# Poseidon.net
KiCad netlist of a schematic drawn in EAGLE
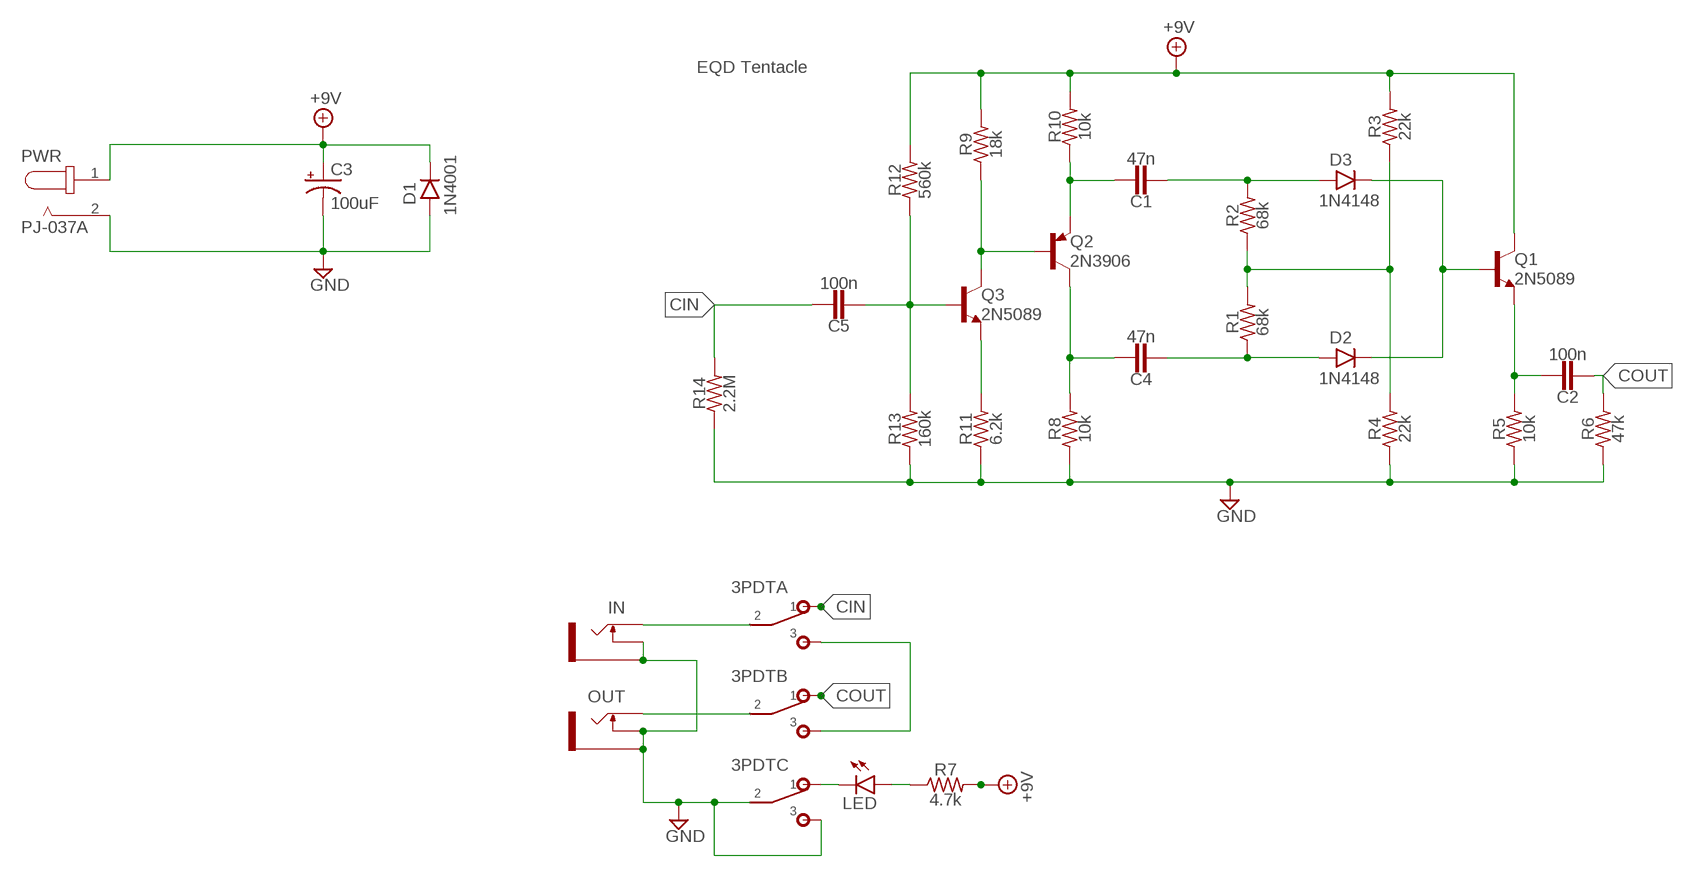
[diagram p0: schematic, sheet 1]

(export (version "E")
  (design (tool "Eeschema 10.0.6"))
  (components
    (comp (ref "3PDT")
      (value "3PDT")
      (footprint "eagle-import:3PDT")
      (libsource (lib "eagle-import") (part "3PDT"))
    )
    (comp (ref "C1")
      (value "47n")
      (footprint "eagle-import:0.2_.SML")
      (libsource (lib "eagle-import") (part "CAP.2"))
    )
    (comp (ref "C2")
      (value "100n")
      (footprint "eagle-import:0.2_.SML")
      (libsource (lib "eagle-import") (part "CAP.2"))
    )
    (comp (ref "C3")
      (value "100uF")
      (footprint "eagle-import:063_025")
      (libsource (lib "eagle-import") (part "0631"))
    )
    (comp (ref "C4")
      (value "47n")
      (footprint "eagle-import:0.2_.SML")
      (libsource (lib "eagle-import") (part "CAP.2"))
    )
    (comp (ref "C5")
      (value "100n")
      (footprint "eagle-import:0.2_.SML")
      (libsource (lib "eagle-import") (part "CAP.2"))
    )
    (comp (ref "D1")
      (value "1N4001")
      (footprint "eagle-import:DO41-3")
      (libsource (lib "eagle-import") (part "DO41.3"))
    )
    (comp (ref "D2")
      (value "1N4148")
      (footprint "eagle-import:DO35-3")
      (libsource (lib "eagle-import") (part "DO35.3"))
    )
    (comp (ref "D3")
      (value "1N4148")
      (footprint "eagle-import:DO35-3")
      (libsource (lib "eagle-import") (part "DO35.3"))
    )
    (comp (ref "IN")
      (value "NV-PJ3410_MONO")
      (footprint "eagle-import:NV-PJ3410_SOCKET_MONO")
      (libsource (lib "eagle-import") (part "NV-PJ3410_MONO"))
    )
    (comp (ref "LED")
      (value "LED3MM")
      (footprint "eagle-import:LED3MM")
      (libsource (lib "eagle-import") (part "LED3MM"))
    )
    (comp (ref "OUT")
      (value "NV-PJ3410_MONO")
      (footprint "eagle-import:NV-PJ3410_SOCKET_MONO")
      (libsource (lib "eagle-import") (part "NV-PJ3410_MONO"))
    )
    (comp (ref "PWR")
      (value "PJ-037A")
      (footprint "eagle-import:CUI_PJ-037A")
      (fields (field (name "MF") "CUI Devices"))
      (libsource (lib "eagle-import") (part "PJ-037A"))
    )
    (comp (ref "Q1")
      (value "2N5089")
      (footprint "eagle-import:TO92")
      (libsource (lib "eagle-import") (part "2N5088"))
    )
    (comp (ref "Q2")
      (value "2N3906")
      (footprint "eagle-import:TO92")
      (libsource (lib "eagle-import") (part "2N5087"))
    )
    (comp (ref "Q3")
      (value "2N5089")
      (footprint "eagle-import:TO92")
      (libsource (lib "eagle-import") (part "2N5088"))
    )
    (comp (ref "R1")
      (value "68k")
      (footprint "eagle-import:0.3_.B")
      (libsource (lib "eagle-import") (part "R.3B"))
    )
    (comp (ref "R2")
      (value "68k")
      (footprint "eagle-import:0.3_.B")
      (libsource (lib "eagle-import") (part "R.3B"))
    )
    (comp (ref "R3")
      (value "22k")
      (footprint "eagle-import:0.3_.B")
      (libsource (lib "eagle-import") (part "R.3B"))
    )
    (comp (ref "R4")
      (value "22k")
      (footprint "eagle-import:0.3_.B")
      (libsource (lib "eagle-import") (part "R.3B"))
    )
    (comp (ref "R5")
      (value "10k")
      (footprint "eagle-import:0.3_.B")
      (libsource (lib "eagle-import") (part "R.3B"))
    )
    (comp (ref "R6")
      (value "47k")
      (footprint "eagle-import:0.3_.B")
      (libsource (lib "eagle-import") (part "R.3B"))
    )
    (comp (ref "R7")
      (value "4.7k")
      (footprint "eagle-import:0.3_.B")
      (libsource (lib "eagle-import") (part "R.3B"))
    )
    (comp (ref "R8")
      (value "10k")
      (footprint "eagle-import:0.3_.B")
      (libsource (lib "eagle-import") (part "R.3B"))
    )
    (comp (ref "R9")
      (value "18k")
      (footprint "eagle-import:0.3_.B")
      (libsource (lib "eagle-import") (part "R.3B"))
    )
    (comp (ref "R10")
      (value "10k")
      (footprint "eagle-import:0.3_.B")
      (libsource (lib "eagle-import") (part "R.3B"))
    )
    (comp (ref "R11")
      (value "6.2k")
      (footprint "eagle-import:0.3_.B")
      (libsource (lib "eagle-import") (part "R.3B"))
    )
    (comp (ref "R12")
      (value "560k")
      (footprint "eagle-import:0.3_.B")
      (libsource (lib "eagle-import") (part "R.3B"))
    )
    (comp (ref "R13")
      (value "160k")
      (footprint "eagle-import:0.3_.B")
      (libsource (lib "eagle-import") (part "R.3B"))
    )
    (comp (ref "R14")
      (value "2.2M")
      (footprint "eagle-import:0.3_.B")
      (libsource (lib "eagle-import") (part "R.3B"))
    )
  )
  (nets
    (net (code "1") (name "+9V") (class "Default")
      (node (ref "C3") (pin "+") (pinfunction "+_+") (pintype "passive"))
      (node (ref "D1") (pin "C") (pinfunction "C_C") (pintype "passive"))
      (node (ref "PWR") (pin "1") (pinfunction "1_1") (pintype "passive"))
      (node (ref "Q1") (pin "1") (pinfunction "C_1") (pintype "passive"))
      (node (ref "R10") (pin "2") (pinfunction "2_2") (pintype "passive"))
      (node (ref "R12") (pin "2") (pinfunction "2_2") (pintype "passive"))
      (node (ref "R3") (pin "2") (pinfunction "2_2") (pintype "passive"))
      (node (ref "R7") (pin "2") (pinfunction "2_2") (pintype "passive"))
      (node (ref "R9") (pin "2") (pinfunction "2_2") (pintype "passive"))
    )
    (net (code "2") (name "CIN") (class "Default")
      (node (ref "3PDT") (pin "A1") (pinfunction "1_A1") (pintype "passive"))
      (node (ref "C5") (pin "1") (pinfunction "1_1") (pintype "passive"))
      (node (ref "R14") (pin "2") (pinfunction "2_2") (pintype "passive"))
    )
    (net (code "3") (name "COUT") (class "Default")
      (node (ref "3PDT") (pin "B1") (pinfunction "1_B1") (pintype "passive"))
      (node (ref "C2") (pin "2") (pinfunction "2_2") (pintype "passive"))
      (node (ref "R6") (pin "2") (pinfunction "2_2") (pintype "passive"))
    )
    (net (code "4") (name "GND") (class "Default")
      (node (ref "3PDT") (pin "C2") (pinfunction "2_C2") (pintype "passive"))
      (node (ref "3PDT") (pin "C3") (pinfunction "3_C3") (pintype "passive"))
      (node (ref "C3") (pin "-") (pinfunction "-_-") (pintype "passive"))
      (node (ref "D1") (pin "A") (pinfunction "A_A") (pintype "passive"))
      (node (ref "IN") (pin "GND") (pinfunction "SLEEVE_GND") (pintype "passive"))
      (node (ref "IN") (pin "SWITCH") (pinfunction "SWITCH_SWITCH") (pintype "passive"))
      (node (ref "OUT") (pin "GND") (pinfunction "SLEEVE_GND") (pintype "passive"))
      (node (ref "OUT") (pin "SWITCH") (pinfunction "SWITCH_SWITCH") (pintype "passive"))
      (node (ref "PWR") (pin "2") (pinfunction "2_2") (pintype "passive"))
      (node (ref "R11") (pin "1") (pinfunction "1_1") (pintype "passive"))
      (node (ref "R13") (pin "1") (pinfunction "1_1") (pintype "passive"))
      (node (ref "R14") (pin "1") (pinfunction "1_1") (pintype "passive"))
      (node (ref "R4") (pin "1") (pinfunction "1_1") (pintype "passive"))
      (node (ref "R5") (pin "1") (pinfunction "1_1") (pintype "passive"))
      (node (ref "R6") (pin "1") (pinfunction "1_1") (pintype "passive"))
      (node (ref "R8") (pin "1") (pinfunction "1_1") (pintype "passive"))
    )
    (net (code "5") (name "Net-(3PDTA-2)") (class "Default")
      (node (ref "3PDT") (pin "A2") (pinfunction "2_A2") (pintype "passive"))
      (node (ref "IN") (pin "LEFT") (pinfunction "TIP_LEFT") (pintype "passive"))
    )
    (net (code "6") (name "Net-(3PDTA-3)") (class "Default")
      (node (ref "3PDT") (pin "A3") (pinfunction "3_A3") (pintype "passive"))
      (node (ref "3PDT") (pin "B3") (pinfunction "3_B3") (pintype "passive"))
    )
    (net (code "7") (name "Net-(3PDTB-2)") (class "Default")
      (node (ref "3PDT") (pin "B2") (pinfunction "2_B2") (pintype "passive"))
      (node (ref "OUT") (pin "LEFT") (pinfunction "TIP_LEFT") (pintype "passive"))
    )
    (net (code "8") (name "Net-(3PDTC-1)") (class "Default")
      (node (ref "3PDT") (pin "C1") (pinfunction "1_C1") (pintype "passive"))
      (node (ref "LED") (pin "K") (pinfunction "C_K") (pintype "passive"))
    )
    (net (code "9") (name "Net-(C1-Pad2)") (class "Default")
      (node (ref "C1") (pin "2") (pinfunction "2_2") (pintype "passive"))
      (node (ref "D3") (pin "A") (pinfunction "A_A") (pintype "passive"))
      (node (ref "R2") (pin "2") (pinfunction "2_2") (pintype "passive"))
    )
    (net (code "10") (name "Net-(C4-Pad2)") (class "Default")
      (node (ref "C4") (pin "2") (pinfunction "2_2") (pintype "passive"))
      (node (ref "D2") (pin "A") (pinfunction "A_A") (pintype "passive"))
      (node (ref "R1") (pin "1") (pinfunction "1_1") (pintype "passive"))
    )
    (net (code "11") (name "Net-(LED-PadA)") (class "Default")
      (node (ref "LED") (pin "A") (pinfunction "A_A") (pintype "passive"))
      (node (ref "R7") (pin "1") (pinfunction "1_1") (pintype "passive"))
    )
    (net (code "12") (name "Net-(Q1-B)") (class "Default")
      (node (ref "D2") (pin "C") (pinfunction "C_C") (pintype "passive"))
      (node (ref "D3") (pin "C") (pinfunction "C_C") (pintype "passive"))
      (node (ref "Q1") (pin "2") (pinfunction "B_2") (pintype "passive"))
    )
    (net (code "13") (name "Net-(Q1-E)") (class "Default")
      (node (ref "C2") (pin "1") (pinfunction "1_1") (pintype "passive"))
      (node (ref "Q1") (pin "3") (pinfunction "E_3") (pintype "passive"))
      (node (ref "R5") (pin "2") (pinfunction "2_2") (pintype "passive"))
    )
    (net (code "14") (name "Net-(Q2-B)") (class "Default")
      (node (ref "Q2") (pin "2") (pinfunction "B_2") (pintype "passive"))
      (node (ref "Q3") (pin "1") (pinfunction "C_1") (pintype "passive"))
      (node (ref "R9") (pin "1") (pinfunction "1_1") (pintype "passive"))
    )
    (net (code "15") (name "Net-(Q2-C)") (class "Default")
      (node (ref "C4") (pin "1") (pinfunction "1_1") (pintype "passive"))
      (node (ref "Q2") (pin "1") (pinfunction "C_1") (pintype "passive"))
      (node (ref "R8") (pin "2") (pinfunction "2_2") (pintype "passive"))
    )
    (net (code "16") (name "Net-(Q2-E)") (class "Default")
      (node (ref "C1") (pin "1") (pinfunction "1_1") (pintype "passive"))
      (node (ref "Q2") (pin "3") (pinfunction "E_3") (pintype "passive"))
      (node (ref "R10") (pin "1") (pinfunction "1_1") (pintype "passive"))
    )
    (net (code "17") (name "Net-(Q3-B)") (class "Default")
      (node (ref "C5") (pin "2") (pinfunction "2_2") (pintype "passive"))
      (node (ref "Q3") (pin "2") (pinfunction "B_2") (pintype "passive"))
      (node (ref "R12") (pin "1") (pinfunction "1_1") (pintype "passive"))
      (node (ref "R13") (pin "2") (pinfunction "2_2") (pintype "passive"))
    )
    (net (code "18") (name "Net-(Q3-E)") (class "Default")
      (node (ref "Q3") (pin "3") (pinfunction "E_3") (pintype "passive"))
      (node (ref "R11") (pin "2") (pinfunction "2_2") (pintype "passive"))
    )
    (net (code "19") (name "Net-(R1-Pad2)") (class "Default")
      (node (ref "R1") (pin "2") (pinfunction "2_2") (pintype "passive"))
      (node (ref "R2") (pin "1") (pinfunction "1_1") (pintype "passive"))
      (node (ref "R3") (pin "1") (pinfunction "1_1") (pintype "passive"))
      (node (ref "R4") (pin "2") (pinfunction "2_2") (pintype "passive"))
    )
  )
)
